# Meshtastic-DIY_v4_TTGO-T8-18.net
KiCad netlist of a schematic drawn in EAGLE
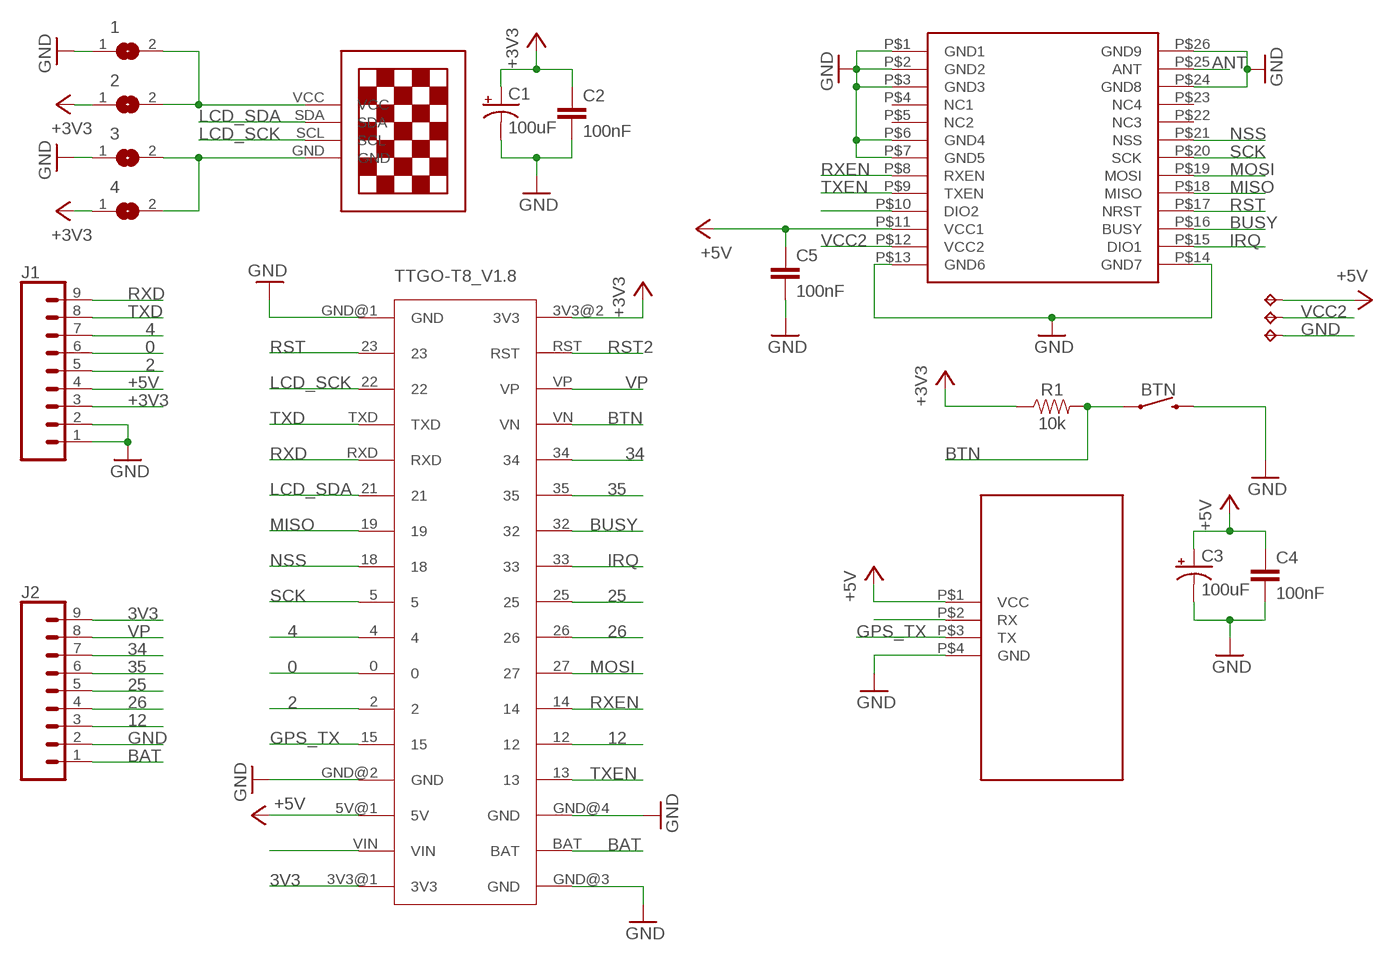
[diagram p0: schematic, sheet 1]

(export (version "E")
  (design (tool "Eeschema 10.0.6"))
  (components
    (comp (ref "1") (value "SJ") (footprint "eagle-import:SJ") (libsource (lib "eagle-import") (part "SJ")))
    (comp (ref "2") (value "SJ") (footprint "eagle-import:SJ") (libsource (lib "eagle-import") (part "SJ")))
    (comp (ref "3") (value "SJ") (footprint "eagle-import:SJ") (libsource (lib "eagle-import") (part "SJ")))
    (comp (ref "4") (value "SJ") (footprint "eagle-import:SJ") (libsource (lib "eagle-import") (part "SJ")))
    (comp (ref "BTN")
      (value "MOMENTARY-SWITCH-SPST-SMD-5.2MM")
      (footprint "eagle-import:TACTILE_SWITCH_SMD_5.2MM")
      (libsource (lib "eagle-import") (part "MOMENTARY-SWITCH-SPST-SMD-5.2MM"))
    )
    (comp (ref "C1")
      (value "100uF")
      (footprint "eagle-import:EIA7343")
      (libsource (lib "eagle-import") (part "100UF-POLAR-EIA7343-10V-10%(TANT)"))
    )
    (comp (ref "C2")
      (value "100nF")
      (footprint "eagle-import:0805")
      (libsource (lib "eagle-import") (part "0.33UF/330NF-0805-50V-10%"))
    )
    (comp (ref "C3")
      (value "100uF")
      (footprint "eagle-import:EIA7343")
      (libsource (lib "eagle-import") (part "100UF-POLAR-EIA7343-10V-10%(TANT)"))
    )
    (comp (ref "C4")
      (value "100nF")
      (footprint "eagle-import:0805")
      (libsource (lib "eagle-import") (part "0.33UF/330NF-0805-50V-10%"))
    )
    (comp (ref "C5")
      (value "100nF")
      (footprint "eagle-import:0805")
      (libsource (lib "eagle-import") (part "0.33UF/330NF-0805-50V-10%"))
    )
    (comp (ref "J1")
      (value "CONN_09NO_SILK")
      (footprint "eagle-import:1X09_NO_SILK")
      (libsource (lib "eagle-import") (part "CONN_09NO_SILK"))
    )
    (comp (ref "J2")
      (value "CONN_09NO_SILK")
      (footprint "eagle-import:1X09_NO_SILK")
      (libsource (lib "eagle-import") (part "CONN_09NO_SILK"))
    )
    (comp (ref "R1")
      (value "10k")
      (footprint "eagle-import:1210")
      (libsource (lib "eagle-import") (part "0.1OHM-1210-1/2W-1%"))
    )
    (comp (ref "TP1")
      (value "TPTP14SQ")
      (footprint "eagle-import:TP14SQ")
      (libsource (lib "eagle-import") (part "TPTP14SQ"))
    )
    (comp (ref "TP2")
      (value "TPTP14SQ")
      (footprint "eagle-import:TP14SQ")
      (libsource (lib "eagle-import") (part "TPTP14SQ"))
    )
    (comp (ref "TP3")
      (value "TPTP14SQ")
      (footprint "eagle-import:TP14SQ")
      (libsource (lib "eagle-import") (part "TPTP14SQ"))
    )
    (comp (ref "TTGO-T8_V1.8")
      (value "TTGO-T8_V18")
      (footprint "eagle-import:TTGO-T8_V18")
      (libsource (lib "eagle-import") (part "TTGO-T8_V18"))
    )
    (comp (ref "U$1")
      (value "13\"OLED13\"OLED")
      (footprint "eagle-import:1.3_OLED")
      (libsource (lib "eagle-import") (part "13{dblquote}OLED13{dblquote}OLED"))
    )
    (comp (ref "U$2")
      (value "E22-XXXMXXS")
      (footprint "eagle-import:E22-XXXMXXS")
      (libsource (lib "eagle-import") (part "E22-XXXMXXS"))
    )
    (comp (ref "U$3")
      (value "GPS-NEO")
      (footprint "eagle-import:GPS-NEO")
      (libsource (lib "eagle-import") (part "GPS-NEO"))
    )
  )
  (nets
    (net (code "1") (name "+3V3") (class "Default")
      (node (ref "2") (pin "1") (pinfunction "1_1") (pintype "passive"))
      (node (ref "4") (pin "1") (pinfunction "1_1") (pintype "passive"))
      (node (ref "C1") (pin "A") (pinfunction "+_A") (pintype "passive"))
      (node (ref "C2") (pin "1") (pinfunction "1_1") (pintype "passive"))
      (node (ref "J1") (pin "3") (pinfunction "3_3") (pintype "passive"))
      (node (ref "R1") (pin "1") (pinfunction "1_1") (pintype "passive"))
      (node (ref "TTGO-T8_V1.8") (pin "3V3@2") (pinfunction "3V3_3V3@2") (pintype "bidirectional"))
    )
    (net (code "2") (name "+5V") (class "Default")
      (node (ref "C3") (pin "A") (pinfunction "+_A") (pintype "passive"))
      (node (ref "C4") (pin "1") (pinfunction "1_1") (pintype "passive"))
      (node (ref "C5") (pin "1") (pinfunction "1_1") (pintype "passive"))
      (node (ref "J1") (pin "4") (pinfunction "4_4") (pintype "passive"))
      (node (ref "TP1") (pin "TP") (pinfunction "TP_TP") (pintype "input"))
      (node (ref "TTGO-T8_V1.8") (pin "5V@1") (pinfunction "5V_5V@1") (pintype "bidirectional"))
      (node (ref "U$2") (pin "P$11") (pinfunction "VCC1_P$11") (pintype "bidirectional"))
      (node (ref "U$3") (pin "P$1") (pinfunction "VCC_P$1") (pintype "bidirectional"))
    )
    (net (code "3") (name "/0") (class "Default")
      (node (ref "J1") (pin "6") (pinfunction "6_6") (pintype "passive"))
      (node (ref "TTGO-T8_V1.8") (pin "0") (pinfunction "0_0") (pintype "bidirectional"))
    )
    (net (code "4") (name "/2") (class "Default")
      (node (ref "J1") (pin "5") (pinfunction "5_5") (pintype "passive"))
      (node (ref "TTGO-T8_V1.8") (pin "2") (pinfunction "2_2") (pintype "bidirectional"))
    )
    (net (code "5") (name "/3V3") (class "Default")
      (node (ref "J2") (pin "9") (pinfunction "9_9") (pintype "passive"))
      (node (ref "TTGO-T8_V1.8") (pin "3V3@1") (pinfunction "3V3_3V3@1") (pintype "bidirectional"))
    )
    (net (code "6") (name "/4") (class "Default")
      (node (ref "J1") (pin "7") (pinfunction "7_7") (pintype "passive"))
      (node (ref "TTGO-T8_V1.8") (pin "4") (pinfunction "4_4") (pintype "bidirectional"))
    )
    (net (code "7") (name "/12") (class "Default")
      (node (ref "J2") (pin "3") (pinfunction "3_3") (pintype "passive"))
      (node (ref "TTGO-T8_V1.8") (pin "12") (pinfunction "12_12") (pintype "bidirectional"))
    )
    (net (code "8") (name "/25") (class "Default")
      (node (ref "J2") (pin "5") (pinfunction "5_5") (pintype "passive"))
      (node (ref "TTGO-T8_V1.8") (pin "25") (pinfunction "25_25") (pintype "bidirectional"))
    )
    (net (code "9") (name "/26") (class "Default")
      (node (ref "J2") (pin "4") (pinfunction "4_4") (pintype "passive"))
      (node (ref "TTGO-T8_V1.8") (pin "26") (pinfunction "26_26") (pintype "bidirectional"))
    )
    (net (code "10") (name "/34") (class "Default")
      (node (ref "J2") (pin "7") (pinfunction "7_7") (pintype "passive"))
      (node (ref "TTGO-T8_V1.8") (pin "34") (pinfunction "34_34") (pintype "bidirectional"))
    )
    (net (code "11") (name "/35") (class "Default")
      (node (ref "J2") (pin "6") (pinfunction "6_6") (pintype "passive"))
      (node (ref "TTGO-T8_V1.8") (pin "35") (pinfunction "35_35") (pintype "bidirectional"))
    )
    (net (code "12") (name "/ANT") (class "Default")
      (node (ref "U$2") (pin "P$25") (pinfunction "ANT_P$25") (pintype "bidirectional"))
    )
    (net (code "13") (name "/BAT") (class "Default")
      (node (ref "J2") (pin "1") (pinfunction "1_1") (pintype "passive"))
      (node (ref "TTGO-T8_V1.8") (pin "BAT") (pinfunction "BAT_BAT") (pintype "bidirectional"))
    )
    (net (code "14") (name "/BTN") (class "Default")
      (node (ref "BTN") (pin "1") (pinfunction "1_1") (pintype "passive"))
      (node (ref "R1") (pin "2") (pinfunction "2_2") (pintype "passive"))
      (node (ref "TTGO-T8_V1.8") (pin "VN") (pinfunction "VN_VN") (pintype "bidirectional"))
    )
    (net (code "15") (name "/BUSY") (class "Default")
      (node (ref "TTGO-T8_V1.8") (pin "32") (pinfunction "32_32") (pintype "bidirectional"))
      (node (ref "U$2") (pin "P$16") (pinfunction "BUSY_P$16") (pintype "bidirectional"))
    )
    (net (code "16") (name "/GPS_TX") (class "Default")
      (node (ref "TTGO-T8_V1.8") (pin "15") (pinfunction "15_15") (pintype "bidirectional"))
      (node (ref "U$3") (pin "P$3") (pinfunction "TX_P$3") (pintype "bidirectional"))
    )
    (net (code "17") (name "/IRQ") (class "Default")
      (node (ref "TTGO-T8_V1.8") (pin "33") (pinfunction "33_33") (pintype "bidirectional"))
      (node (ref "U$2") (pin "P$15") (pinfunction "DIO1_P$15") (pintype "bidirectional"))
    )
    (net (code "18") (name "/LCD_SCK") (class "Default")
      (node (ref "TTGO-T8_V1.8") (pin "22") (pinfunction "22_22") (pintype "bidirectional"))
      (node (ref "U$1") (pin "SCL") (pinfunction "SCL_SCL") (pintype "bidirectional"))
    )
    (net (code "19") (name "/LCD_SDA") (class "Default")
      (node (ref "TTGO-T8_V1.8") (pin "21") (pinfunction "21_21") (pintype "bidirectional"))
      (node (ref "U$1") (pin "SDA") (pinfunction "SDA_SDA") (pintype "bidirectional"))
    )
    (net (code "20") (name "/MISO") (class "Default")
      (node (ref "TTGO-T8_V1.8") (pin "19") (pinfunction "19_19") (pintype "bidirectional"))
      (node (ref "U$2") (pin "P$18") (pinfunction "MISO_P$18") (pintype "bidirectional"))
    )
    (net (code "21") (name "/MOSI") (class "Default")
      (node (ref "TTGO-T8_V1.8") (pin "27") (pinfunction "27_27") (pintype "bidirectional"))
      (node (ref "U$2") (pin "P$19") (pinfunction "MOSI_P$19") (pintype "bidirectional"))
    )
    (net (code "22") (name "/NSS") (class "Default")
      (node (ref "TTGO-T8_V1.8") (pin "18") (pinfunction "18_18") (pintype "bidirectional"))
      (node (ref "U$2") (pin "P$21") (pinfunction "NSS_P$21") (pintype "bidirectional"))
    )
    (net (code "23") (name "/RST") (class "Default")
      (node (ref "TTGO-T8_V1.8") (pin "23") (pinfunction "23_23") (pintype "bidirectional"))
      (node (ref "U$2") (pin "P$17") (pinfunction "NRST_P$17") (pintype "bidirectional"))
    )
    (net (code "24") (name "/RST2") (class "Default")
      (node (ref "TTGO-T8_V1.8") (pin "RST") (pinfunction "RST_RST") (pintype "bidirectional"))
    )
    (net (code "25") (name "/RXD") (class "Default")
      (node (ref "J1") (pin "9") (pinfunction "9_9") (pintype "passive"))
      (node (ref "TTGO-T8_V1.8") (pin "RXD") (pinfunction "RXD_RXD") (pintype "bidirectional"))
    )
    (net (code "26") (name "/RXEN") (class "Default")
      (node (ref "TTGO-T8_V1.8") (pin "14") (pinfunction "14_14") (pintype "bidirectional"))
      (node (ref "U$2") (pin "P$8") (pinfunction "RXEN_P$8") (pintype "bidirectional"))
    )
    (net (code "27") (name "/SCK") (class "Default")
      (node (ref "TTGO-T8_V1.8") (pin "5") (pinfunction "5_5") (pintype "bidirectional"))
      (node (ref "U$2") (pin "P$20") (pinfunction "SCK_P$20") (pintype "bidirectional"))
    )
    (net (code "28") (name "/TXD") (class "Default")
      (node (ref "J1") (pin "8") (pinfunction "8_8") (pintype "passive"))
      (node (ref "TTGO-T8_V1.8") (pin "TXD") (pinfunction "TXD_TXD") (pintype "bidirectional"))
    )
    (net (code "29") (name "/TXEN") (class "Default")
      (node (ref "TTGO-T8_V1.8") (pin "13") (pinfunction "13_13") (pintype "bidirectional"))
      (node (ref "U$2") (pin "P$9") (pinfunction "TXEN_P$9") (pintype "bidirectional"))
    )
    (net (code "30") (name "/VCC2") (class "Default")
      (node (ref "TP2") (pin "TP") (pinfunction "TP_TP") (pintype "input"))
      (node (ref "U$2") (pin "P$12") (pinfunction "VCC2_P$12") (pintype "bidirectional"))
    )
    (net (code "31") (name "/VP") (class "Default")
      (node (ref "J2") (pin "8") (pinfunction "8_8") (pintype "passive"))
      (node (ref "TTGO-T8_V1.8") (pin "VP") (pinfunction "VP_VP") (pintype "bidirectional"))
    )
    (net (code "32") (name "GND") (class "Default")
      (node (ref "1") (pin "1") (pinfunction "1_1") (pintype "passive"))
      (node (ref "3") (pin "1") (pinfunction "1_1") (pintype "passive"))
      (node (ref "BTN") (pin "3") (pinfunction "2_3") (pintype "passive"))
      (node (ref "C1") (pin "C") (pinfunction "-_C") (pintype "passive"))
      (node (ref "C2") (pin "2") (pinfunction "2_2") (pintype "passive"))
      (node (ref "C3") (pin "C") (pinfunction "-_C") (pintype "passive"))
      (node (ref "C4") (pin "2") (pinfunction "2_2") (pintype "passive"))
      (node (ref "C5") (pin "2") (pinfunction "2_2") (pintype "passive"))
      (node (ref "J1") (pin "1") (pinfunction "1_1") (pintype "passive"))
      (node (ref "J1") (pin "2") (pinfunction "2_2") (pintype "passive"))
      (node (ref "J2") (pin "2") (pinfunction "2_2") (pintype "passive"))
      (node (ref "TP3") (pin "TP") (pinfunction "TP_TP") (pintype "input"))
      (node (ref "TTGO-T8_V1.8") (pin "GND@1") (pinfunction "GND_GND@1") (pintype "bidirectional"))
      (node (ref "TTGO-T8_V1.8") (pin "GND@2") (pinfunction "GND_GND@2") (pintype "bidirectional"))
      (node (ref "TTGO-T8_V1.8") (pin "GND@3") (pinfunction "GND_GND@3") (pintype "bidirectional"))
      (node (ref "TTGO-T8_V1.8") (pin "GND@4") (pinfunction "GND_GND@4") (pintype "bidirectional"))
      (node (ref "U$2") (pin "P$1") (pinfunction "GND1_P$1") (pintype "bidirectional"))
      (node (ref "U$2") (pin "P$13") (pinfunction "GND6_P$13") (pintype "bidirectional"))
      (node (ref "U$2") (pin "P$14") (pinfunction "GND7_P$14") (pintype "bidirectional"))
      (node (ref "U$2") (pin "P$2") (pinfunction "GND2_P$2") (pintype "bidirectional"))
      (node (ref "U$2") (pin "P$24") (pinfunction "GND8_P$24") (pintype "bidirectional"))
      (node (ref "U$2") (pin "P$26") (pinfunction "GND9_P$26") (pintype "bidirectional"))
      (node (ref "U$2") (pin "P$3") (pinfunction "GND3_P$3") (pintype "bidirectional"))
      (node (ref "U$2") (pin "P$6") (pinfunction "GND4_P$6") (pintype "bidirectional"))
      (node (ref "U$2") (pin "P$7") (pinfunction "GND5_P$7") (pintype "bidirectional"))
      (node (ref "U$3") (pin "P$4") (pinfunction "GND_P$4") (pintype "bidirectional"))
    )
    (net (code "33") (name "Net-(1-Pad2)") (class "Default")
      (node (ref "1") (pin "2") (pinfunction "2_2") (pintype "passive"))
      (node (ref "2") (pin "2") (pinfunction "2_2") (pintype "passive"))
      (node (ref "U$1") (pin "VCC") (pinfunction "VCC_VCC") (pintype "bidirectional"))
    )
    (net (code "34") (name "Net-(3-Pad2)") (class "Default")
      (node (ref "3") (pin "2") (pinfunction "2_2") (pintype "passive"))
      (node (ref "4") (pin "2") (pinfunction "2_2") (pintype "passive"))
      (node (ref "U$1") (pin "GND") (pinfunction "GND_GND") (pintype "bidirectional"))
    )
    (net (code "35") (name "unconnected-(TTGO-T8_V1.8-PadVIN)") (class "Default")
      (node (ref "TTGO-T8_V1.8") (pin "VIN") (pinfunction "VIN_VIN") (pintype "bidirectional"))
    )
    (net (code "36") (name "unconnected-(U$2-DIO2-PadP$10)") (class "Default")
      (node (ref "U$2") (pin "P$10") (pinfunction "DIO2_P$10") (pintype "bidirectional"))
    )
    (net (code "37") (name "unconnected-(U$2-NC1-PadP$4)") (class "Default")
      (node (ref "U$2") (pin "P$4") (pinfunction "NC1_P$4") (pintype "bidirectional"))
    )
    (net (code "38") (name "unconnected-(U$2-NC2-PadP$5)") (class "Default")
      (node (ref "U$2") (pin "P$5") (pinfunction "NC2_P$5") (pintype "bidirectional"))
    )
    (net (code "39") (name "unconnected-(U$2-NC3-PadP$22)") (class "Default")
      (node (ref "U$2") (pin "P$22") (pinfunction "NC3_P$22") (pintype "bidirectional"))
    )
    (net (code "40") (name "unconnected-(U$2-NC4-PadP$23)") (class "Default")
      (node (ref "U$2") (pin "P$23") (pinfunction "NC4_P$23") (pintype "bidirectional"))
    )
    (net (code "41") (name "unconnected-(U$3-RX-PadP$2)") (class "Default")
      (node (ref "U$3") (pin "P$2") (pinfunction "RX_P$2") (pintype "bidirectional"))
    )
  )
)
